# axiom_beta_plugin_module_1xHDMI.net
KiCad netlist of a schematic drawn in EAGLE
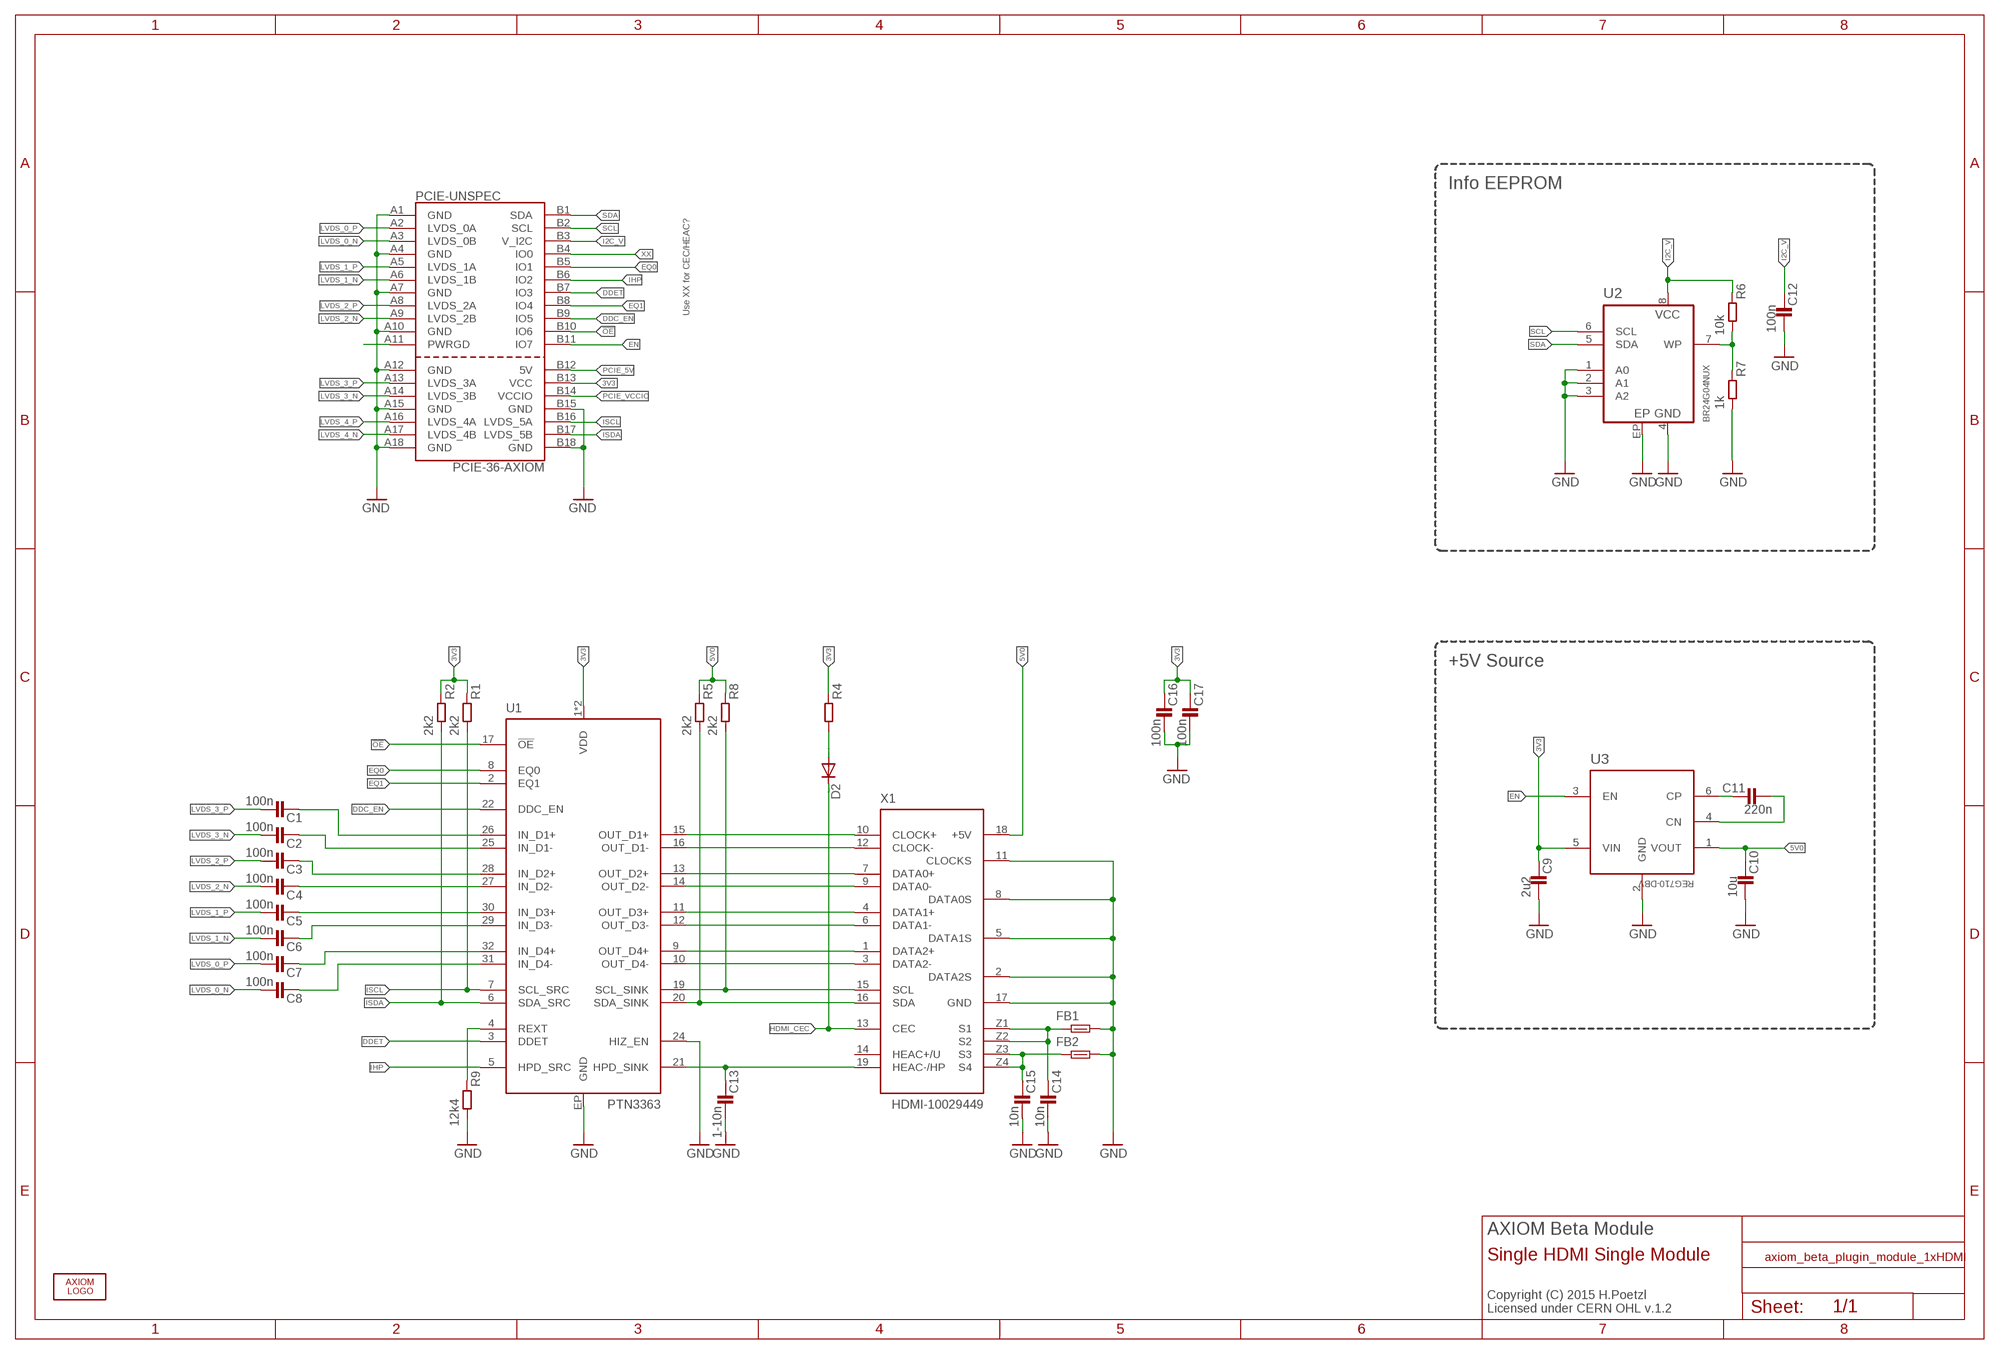
[diagram p0: schematic, sheet 1]

(export (version "E")
  (design (tool "Eeschema 10.0.6"))
  (components
    (comp (ref "C1")
      (value "100n")
      (footprint "eagle-import:0402-C")
      (libsource (lib "eagle-import") (part "C0402-C"))
    )
    (comp (ref "C2")
      (value "100n")
      (footprint "eagle-import:0402-C")
      (libsource (lib "eagle-import") (part "C0402-C"))
    )
    (comp (ref "C3")
      (value "100n")
      (footprint "eagle-import:0402-C")
      (libsource (lib "eagle-import") (part "C0402-C"))
    )
    (comp (ref "C4")
      (value "100n")
      (footprint "eagle-import:0402-C")
      (libsource (lib "eagle-import") (part "C0402-C"))
    )
    (comp (ref "C5")
      (value "100n")
      (footprint "eagle-import:0402-C")
      (libsource (lib "eagle-import") (part "C0402-C"))
    )
    (comp (ref "C6")
      (value "100n")
      (footprint "eagle-import:0402-C")
      (libsource (lib "eagle-import") (part "C0402-C"))
    )
    (comp (ref "C7")
      (value "100n")
      (footprint "eagle-import:0402-C")
      (libsource (lib "eagle-import") (part "C0402-C"))
    )
    (comp (ref "C8")
      (value "100n")
      (footprint "eagle-import:0402-C")
      (libsource (lib "eagle-import") (part "C0402-C"))
    )
    (comp (ref "C9")
      (value "2u2")
      (footprint "eagle-import:0603-B")
      (libsource (lib "eagle-import") (part "C0603-B"))
    )
    (comp (ref "C10")
      (value "10u")
      (footprint "eagle-import:0603-B")
      (libsource (lib "eagle-import") (part "C0603-B"))
    )
    (comp (ref "C11")
      (value "220n")
      (footprint "eagle-import:0603-B")
      (libsource (lib "eagle-import") (part "C0603-B"))
    )
    (comp (ref "C12")
      (value "100n")
      (footprint "eagle-import:0402-B")
      (libsource (lib "eagle-import") (part "C0402-B"))
    )
    (comp (ref "C13")
      (value "1-10n")
      (footprint "eagle-import:0402-B")
      (libsource (lib "eagle-import") (part "C0402-B"))
    )
    (comp (ref "C14")
      (value "10n")
      (footprint "eagle-import:0402-B")
      (libsource (lib "eagle-import") (part "C0402-B"))
    )
    (comp (ref "C15")
      (value "10n")
      (footprint "eagle-import:0402-B")
      (libsource (lib "eagle-import") (part "C0402-B"))
    )
    (comp (ref "C16")
      (value "100n")
      (footprint "eagle-import:0402-B")
      (libsource (lib "eagle-import") (part "C0402-B"))
    )
    (comp (ref "C17")
      (value "100n")
      (footprint "eagle-import:0402-B")
      (libsource (lib "eagle-import") (part "C0402-B"))
    )
    (comp (ref "D2")
      (value "DIODE-SOD523")
      (footprint "eagle-import:SOD523")
      (libsource (lib "eagle-import") (part "DIODE-SOD523"))
    )
    (comp (ref "FB1")
      (value "FB0603-B")
      (footprint "eagle-import:0603-B")
      (libsource (lib "eagle-import") (part "FB0603-B"))
    )
    (comp (ref "FB2")
      (value "FB0603-B")
      (footprint "eagle-import:0603-B")
      (libsource (lib "eagle-import") (part "FB0603-B"))
    )
    (comp (ref "PCIE-UNSPEC")
      (value "PCIE-36-AXIOM")
      (footprint "eagle-import:PCIE-36-AXIOM")
      (libsource (lib "eagle-import") (part "PCIE-36-AXIOM"))
    )
    (comp (ref "R1")
      (value "2k2")
      (footprint "eagle-import:0402-B")
      (libsource (lib "eagle-import") (part "R0402-B"))
    )
    (comp (ref "R2")
      (value "2k2")
      (footprint "eagle-import:0402-B")
      (libsource (lib "eagle-import") (part "R0402-B"))
    )
    (comp (ref "R4")
      (value "R0402-B")
      (footprint "eagle-import:0402-B")
      (libsource (lib "eagle-import") (part "R0402-B"))
    )
    (comp (ref "R5")
      (value "2k2")
      (footprint "eagle-import:0402-B")
      (libsource (lib "eagle-import") (part "R0402-B"))
    )
    (comp (ref "R6")
      (value "10k")
      (footprint "eagle-import:0402-B")
      (libsource (lib "eagle-import") (part "R0402-B"))
    )
    (comp (ref "R7")
      (value "1k")
      (footprint "eagle-import:0402-B")
      (libsource (lib "eagle-import") (part "R0402-B"))
    )
    (comp (ref "R8")
      (value "2k2")
      (footprint "eagle-import:0402-B")
      (libsource (lib "eagle-import") (part "R0402-B"))
    )
    (comp (ref "R9")
      (value "12k4")
      (footprint "eagle-import:0402-B")
      (libsource (lib "eagle-import") (part "R0402-B"))
    )
    (comp (ref "U$1")
      (value "AXIOM_LOGO459X70")
      (footprint "eagle-import:AXIOM_LOGO_459X70")
      (libsource (lib "eagle-import") (part "AXIOM_LOGO459X70"))
    )
    (comp (ref "U1")
      (value "PTN3363")
      (footprint "eagle-import:HVQFN32")
      (libsource (lib "eagle-import") (part "PTN3363"))
    )
    (comp (ref "U2")
      (value "BR24G04NUX")
      (footprint "eagle-import:DFN200X300X100-9N")
      (libsource (lib "eagle-import") (part "BR24G04NUX"))
    )
    (comp (ref "U3")
      (value "REG710-DBV")
      (footprint "eagle-import:DBV")
      (libsource (lib "eagle-import") (part "REG710-DBV"))
    )
    (comp (ref "X1")
      (value "HDMI-10029449")
      (footprint "eagle-import:10029449-X01XLF")
      (libsource (lib "eagle-import") (part "HDMI-10029449"))
    )
  )
  (nets
    (net (code "1") (name "/~{OE}") (class "Default")
      (node (ref "PCIE-UNSPEC") (pin "B10") (pinfunction "IO6_B10") (pintype "passive"))
      (node (ref "U1") (pin "17") (pinfunction "~{OE}_17") (pintype "bidirectional"))
    )
    (net (code "2") (name "3V3") (class "Default")
      (node (ref "C16") (pin "1") (pinfunction "1_1") (pintype "passive"))
      (node (ref "C17") (pin "1") (pinfunction "1_1") (pintype "passive"))
      (node (ref "C9") (pin "1") (pinfunction "1_1") (pintype "passive"))
      (node (ref "PCIE-UNSPEC") (pin "B13") (pinfunction "VCC_B13") (pintype "passive"))
      (node (ref "R1") (pin "1") (pinfunction "1_1") (pintype "passive"))
      (node (ref "R2") (pin "1") (pinfunction "1_1") (pintype "passive"))
      (node (ref "R4") (pin "1") (pinfunction "1_1") (pintype "passive"))
      (node (ref "U1") (pin "1") (pinfunction "VDD_1") (pintype "power_in"))
      (node (ref "U1") (pin "18") (pinfunction "VDD_18") (pintype "power_in"))
      (node (ref "U3") (pin "5") (pinfunction "VIN_5") (pintype "power_in"))
    )
    (net (code "3") (name "5V0") (class "Default")
      (node (ref "C10") (pin "1") (pinfunction "1_1") (pintype "passive"))
      (node (ref "R5") (pin "1") (pinfunction "1_1") (pintype "passive"))
      (node (ref "R8") (pin "1") (pinfunction "1_1") (pintype "passive"))
      (node (ref "U3") (pin "1") (pinfunction "VOUT_1") (pintype "output"))
      (node (ref "X1") (pin "18") (pinfunction "+5V_18") (pintype "power_in"))
    )
    (net (code "4") (name "DDC_EN") (class "Default")
      (node (ref "PCIE-UNSPEC") (pin "B9") (pinfunction "IO5_B9") (pintype "passive"))
      (node (ref "U1") (pin "22") (pinfunction "DDC_EN_22") (pintype "bidirectional"))
    )
    (net (code "5") (name "DDET") (class "Default")
      (node (ref "PCIE-UNSPEC") (pin "B7") (pinfunction "IO3_B7") (pintype "passive"))
      (node (ref "U1") (pin "3") (pinfunction "DDET_3") (pintype "bidirectional"))
    )
    (net (code "6") (name "EN") (class "Default")
      (node (ref "PCIE-UNSPEC") (pin "B11") (pinfunction "IO7_B11") (pintype "passive"))
      (node (ref "U3") (pin "3") (pinfunction "EN_3") (pintype "input"))
    )
    (net (code "7") (name "EQ0") (class "Default")
      (node (ref "PCIE-UNSPEC") (pin "B5") (pinfunction "IO1_B5") (pintype "passive"))
      (node (ref "U1") (pin "8") (pinfunction "EQ0_8") (pintype "bidirectional"))
    )
    (net (code "8") (name "EQ1") (class "Default")
      (node (ref "PCIE-UNSPEC") (pin "B8") (pinfunction "IO4_B8") (pintype "passive"))
      (node (ref "U1") (pin "2") (pinfunction "EQ1_2") (pintype "bidirectional"))
    )
    (net (code "9") (name "GND") (class "Default")
      (node (ref "C10") (pin "2") (pinfunction "2_2") (pintype "passive"))
      (node (ref "C12") (pin "2") (pinfunction "2_2") (pintype "passive"))
      (node (ref "C13") (pin "2") (pinfunction "2_2") (pintype "passive"))
      (node (ref "C14") (pin "2") (pinfunction "2_2") (pintype "passive"))
      (node (ref "C15") (pin "2") (pinfunction "2_2") (pintype "passive"))
      (node (ref "C16") (pin "2") (pinfunction "2_2") (pintype "passive"))
      (node (ref "C17") (pin "2") (pinfunction "2_2") (pintype "passive"))
      (node (ref "C9") (pin "2") (pinfunction "2_2") (pintype "passive"))
      (node (ref "FB1") (pin "2") (pinfunction "2_2") (pintype "passive"))
      (node (ref "FB2") (pin "2") (pinfunction "2_2") (pintype "passive"))
      (node (ref "PCIE-UNSPEC") (pin "A1") (pinfunction "GND_A1") (pintype "passive"))
      (node (ref "PCIE-UNSPEC") (pin "A10") (pinfunction "GND_A10") (pintype "passive"))
      (node (ref "PCIE-UNSPEC") (pin "A12") (pinfunction "GND_A12") (pintype "passive"))
      (node (ref "PCIE-UNSPEC") (pin "A15") (pinfunction "GND_A15") (pintype "passive"))
      (node (ref "PCIE-UNSPEC") (pin "A18") (pinfunction "GND_A18") (pintype "passive"))
      (node (ref "PCIE-UNSPEC") (pin "A4") (pinfunction "GND_A4") (pintype "passive"))
      (node (ref "PCIE-UNSPEC") (pin "A7") (pinfunction "GND_A7") (pintype "passive"))
      (node (ref "PCIE-UNSPEC") (pin "B15") (pinfunction "GND_B15") (pintype "passive"))
      (node (ref "PCIE-UNSPEC") (pin "B18") (pinfunction "GND_B18") (pintype "passive"))
      (node (ref "R7") (pin "2") (pinfunction "2_2") (pintype "passive"))
      (node (ref "R9") (pin "2") (pinfunction "2_2") (pintype "passive"))
      (node (ref "U1") (pin "24") (pinfunction "HIZ_EN_24") (pintype "bidirectional"))
      (node (ref "U1") (pin "EP") (pinfunction "GND_EP") (pintype "bidirectional"))
      (node (ref "U2") (pin "1") (pinfunction "A0_1") (pintype "input"))
      (node (ref "U2") (pin "2") (pinfunction "A1_2") (pintype "input"))
      (node (ref "U2") (pin "3") (pinfunction "A2_3") (pintype "input"))
      (node (ref "U2") (pin "4") (pinfunction "GND_4") (pintype "passive"))
      (node (ref "U2") (pin "EP") (pinfunction "EP_EP") (pintype "passive"))
      (node (ref "U3") (pin "2") (pinfunction "GND_2") (pintype "passive"))
      (node (ref "X1") (pin "11") (pinfunction "CLOCKS_11") (pintype "power_in"))
      (node (ref "X1") (pin "17") (pinfunction "GND_17") (pintype "bidirectional"))
      (node (ref "X1") (pin "2") (pinfunction "DATA2S_2") (pintype "power_in"))
      (node (ref "X1") (pin "5") (pinfunction "DATA1S_5") (pintype "power_in"))
      (node (ref "X1") (pin "8") (pinfunction "DATA0S_8") (pintype "power_in"))
    )
    (net (code "10") (name "HDMI_CEC") (class "Default")
      (node (ref "D2") (pin "C") (pinfunction "C_C") (pintype "passive"))
      (node (ref "X1") (pin "13") (pinfunction "CEC_13") (pintype "bidirectional"))
    )
    (net (code "11") (name "I2C_V") (class "Default")
      (node (ref "C12") (pin "1") (pinfunction "1_1") (pintype "passive"))
      (node (ref "PCIE-UNSPEC") (pin "B3") (pinfunction "V_I2C_B3") (pintype "passive"))
      (node (ref "R6") (pin "1") (pinfunction "1_1") (pintype "passive"))
      (node (ref "U2") (pin "8") (pinfunction "VCC_8") (pintype "power_in"))
    )
    (net (code "12") (name "IHP") (class "Default")
      (node (ref "PCIE-UNSPEC") (pin "B6") (pinfunction "IO2_B6") (pintype "passive"))
      (node (ref "U1") (pin "5") (pinfunction "HPD_SRC_5") (pintype "bidirectional"))
    )
    (net (code "13") (name "ISCL") (class "Default")
      (node (ref "PCIE-UNSPEC") (pin "B16") (pinfunction "LVDS_5A_B16") (pintype "passive"))
      (node (ref "R1") (pin "2") (pinfunction "2_2") (pintype "passive"))
      (node (ref "U1") (pin "7") (pinfunction "SCL_SRC_7") (pintype "bidirectional"))
    )
    (net (code "14") (name "ISDA") (class "Default")
      (node (ref "PCIE-UNSPEC") (pin "B17") (pinfunction "LVDS_5B_B17") (pintype "passive"))
      (node (ref "R2") (pin "2") (pinfunction "2_2") (pintype "passive"))
      (node (ref "U1") (pin "6") (pinfunction "SDA_SRC_6") (pintype "bidirectional"))
    )
    (net (code "15") (name "LVDS_0_N") (class "Default")
      (node (ref "C8") (pin "2") (pinfunction "2_2") (pintype "passive"))
      (node (ref "PCIE-UNSPEC") (pin "A3") (pinfunction "LVDS_0B_A3") (pintype "passive"))
    )
    (net (code "16") (name "LVDS_0_P") (class "Default")
      (node (ref "C7") (pin "2") (pinfunction "2_2") (pintype "passive"))
      (node (ref "PCIE-UNSPEC") (pin "A2") (pinfunction "LVDS_0A_A2") (pintype "passive"))
    )
    (net (code "17") (name "LVDS_1_N") (class "Default")
      (node (ref "C6") (pin "2") (pinfunction "2_2") (pintype "passive"))
      (node (ref "PCIE-UNSPEC") (pin "A6") (pinfunction "LVDS_1B_A6") (pintype "passive"))
    )
    (net (code "18") (name "LVDS_1_P") (class "Default")
      (node (ref "C5") (pin "2") (pinfunction "2_2") (pintype "passive"))
      (node (ref "PCIE-UNSPEC") (pin "A5") (pinfunction "LVDS_1A_A5") (pintype "passive"))
    )
    (net (code "19") (name "LVDS_2_N") (class "Default")
      (node (ref "C4") (pin "2") (pinfunction "2_2") (pintype "passive"))
      (node (ref "PCIE-UNSPEC") (pin "A9") (pinfunction "LVDS_2B_A9") (pintype "passive"))
    )
    (net (code "20") (name "LVDS_2_P") (class "Default")
      (node (ref "C3") (pin "2") (pinfunction "2_2") (pintype "passive"))
      (node (ref "PCIE-UNSPEC") (pin "A8") (pinfunction "LVDS_2A_A8") (pintype "passive"))
    )
    (net (code "21") (name "LVDS_3_N") (class "Default")
      (node (ref "C2") (pin "2") (pinfunction "2_2") (pintype "passive"))
      (node (ref "PCIE-UNSPEC") (pin "A14") (pinfunction "LVDS_3B_A14") (pintype "passive"))
    )
    (net (code "22") (name "LVDS_3_P") (class "Default")
      (node (ref "C1") (pin "2") (pinfunction "2_2") (pintype "passive"))
      (node (ref "PCIE-UNSPEC") (pin "A13") (pinfunction "LVDS_3A_A13") (pintype "passive"))
    )
    (net (code "23") (name "LVDS_4_N") (class "Default")
      (node (ref "PCIE-UNSPEC") (pin "A17") (pinfunction "LVDS_4B_A17") (pintype "passive"))
    )
    (net (code "24") (name "LVDS_4_P") (class "Default")
      (node (ref "PCIE-UNSPEC") (pin "A16") (pinfunction "LVDS_4A_A16") (pintype "passive"))
    )
    (net (code "25") (name "Net-(D2-PadA)") (class "Default")
      (node (ref "D2") (pin "A") (pinfunction "A_A") (pintype "passive"))
      (node (ref "R4") (pin "2") (pinfunction "2_2") (pintype "passive"))
    )
    (net (code "26") (name "Net-(U1-HPD_SINK)") (class "Default")
      (node (ref "C13") (pin "1") (pinfunction "1_1") (pintype "passive"))
      (node (ref "U1") (pin "21") (pinfunction "HPD_SINK_21") (pintype "bidirectional"))
      (node (ref "X1") (pin "19") (pinfunction "HEAC-/HP_19") (pintype "bidirectional"))
    )
    (net (code "27") (name "Net-(U1-IN_D1+)") (class "Default")
      (node (ref "C1") (pin "1") (pinfunction "1_1") (pintype "passive"))
      (node (ref "U1") (pin "26") (pinfunction "IN_D1+_26") (pintype "bidirectional"))
    )
    (net (code "28") (name "Net-(U1-IN_D1-)") (class "Default")
      (node (ref "C2") (pin "1") (pinfunction "1_1") (pintype "passive"))
      (node (ref "U1") (pin "25") (pinfunction "IN_D1-_25") (pintype "bidirectional"))
    )
    (net (code "29") (name "Net-(U1-IN_D2+)") (class "Default")
      (node (ref "C3") (pin "1") (pinfunction "1_1") (pintype "passive"))
      (node (ref "U1") (pin "28") (pinfunction "IN_D2+_28") (pintype "bidirectional"))
    )
    (net (code "30") (name "Net-(U1-IN_D2-)") (class "Default")
      (node (ref "C4") (pin "1") (pinfunction "1_1") (pintype "passive"))
      (node (ref "U1") (pin "27") (pinfunction "IN_D2-_27") (pintype "bidirectional"))
    )
    (net (code "31") (name "Net-(U1-IN_D3+)") (class "Default")
      (node (ref "C5") (pin "1") (pinfunction "1_1") (pintype "passive"))
      (node (ref "U1") (pin "30") (pinfunction "IN_D3+_30") (pintype "bidirectional"))
    )
    (net (code "32") (name "Net-(U1-IN_D3-)") (class "Default")
      (node (ref "C6") (pin "1") (pinfunction "1_1") (pintype "passive"))
      (node (ref "U1") (pin "29") (pinfunction "IN_D3-_29") (pintype "bidirectional"))
    )
    (net (code "33") (name "Net-(U1-IN_D4+)") (class "Default")
      (node (ref "C7") (pin "1") (pinfunction "1_1") (pintype "passive"))
      (node (ref "U1") (pin "32") (pinfunction "IN_D4+_32") (pintype "bidirectional"))
    )
    (net (code "34") (name "Net-(U1-IN_D4-)") (class "Default")
      (node (ref "C8") (pin "1") (pinfunction "1_1") (pintype "passive"))
      (node (ref "U1") (pin "31") (pinfunction "IN_D4-_31") (pintype "bidirectional"))
    )
    (net (code "35") (name "Net-(U1-OUT_D1+)") (class "Default")
      (node (ref "U1") (pin "15") (pinfunction "OUT_D1+_15") (pintype "bidirectional"))
      (node (ref "X1") (pin "10") (pinfunction "CLOCK+_10") (pintype "bidirectional"))
    )
    (net (code "36") (name "Net-(U1-OUT_D1-)") (class "Default")
      (node (ref "U1") (pin "16") (pinfunction "OUT_D1-_16") (pintype "bidirectional"))
      (node (ref "X1") (pin "12") (pinfunction "CLOCK-_12") (pintype "bidirectional"))
    )
    (net (code "37") (name "Net-(U1-OUT_D2+)") (class "Default")
      (node (ref "U1") (pin "13") (pinfunction "OUT_D2+_13") (pintype "bidirectional"))
      (node (ref "X1") (pin "7") (pinfunction "DATA0+_7") (pintype "bidirectional"))
    )
    (net (code "38") (name "Net-(U1-OUT_D2-)") (class "Default")
      (node (ref "U1") (pin "14") (pinfunction "OUT_D2-_14") (pintype "bidirectional"))
      (node (ref "X1") (pin "9") (pinfunction "DATA0-_9") (pintype "bidirectional"))
    )
    (net (code "39") (name "Net-(U1-OUT_D3+)") (class "Default")
      (node (ref "U1") (pin "11") (pinfunction "OUT_D3+_11") (pintype "bidirectional"))
      (node (ref "X1") (pin "4") (pinfunction "DATA1+_4") (pintype "bidirectional"))
    )
    (net (code "40") (name "Net-(U1-OUT_D3-)") (class "Default")
      (node (ref "U1") (pin "12") (pinfunction "OUT_D3-_12") (pintype "bidirectional"))
      (node (ref "X1") (pin "6") (pinfunction "DATA1-_6") (pintype "bidirectional"))
    )
    (net (code "41") (name "Net-(U1-OUT_D4+)") (class "Default")
      (node (ref "U1") (pin "9") (pinfunction "OUT_D4+_9") (pintype "bidirectional"))
      (node (ref "X1") (pin "1") (pinfunction "DATA2+_1") (pintype "bidirectional"))
    )
    (net (code "42") (name "Net-(U1-OUT_D4-)") (class "Default")
      (node (ref "U1") (pin "10") (pinfunction "OUT_D4-_10") (pintype "bidirectional"))
      (node (ref "X1") (pin "3") (pinfunction "DATA2-_3") (pintype "bidirectional"))
    )
    (net (code "43") (name "Net-(U1-REXT)") (class "Default")
      (node (ref "R9") (pin "1") (pinfunction "1_1") (pintype "passive"))
      (node (ref "U1") (pin "4") (pinfunction "REXT_4") (pintype "bidirectional"))
    )
    (net (code "44") (name "Net-(U1-SCL_SINK)") (class "Default")
      (node (ref "R8") (pin "2") (pinfunction "2_2") (pintype "passive"))
      (node (ref "U1") (pin "19") (pinfunction "SCL_SINK_19") (pintype "bidirectional"))
      (node (ref "X1") (pin "15") (pinfunction "SCL_15") (pintype "bidirectional"))
    )
    (net (code "45") (name "Net-(U1-SDA_SINK)") (class "Default")
      (node (ref "R5") (pin "2") (pinfunction "2_2") (pintype "passive"))
      (node (ref "U1") (pin "20") (pinfunction "SDA_SINK_20") (pintype "bidirectional"))
      (node (ref "X1") (pin "16") (pinfunction "SDA_16") (pintype "bidirectional"))
    )
    (net (code "46") (name "Net-(U2-WP)") (class "Default")
      (node (ref "R6") (pin "2") (pinfunction "2_2") (pintype "passive"))
      (node (ref "R7") (pin "1") (pinfunction "1_1") (pintype "passive"))
      (node (ref "U2") (pin "7") (pinfunction "WP_7") (pintype "input"))
    )
    (net (code "47") (name "Net-(U3-CN)") (class "Default")
      (node (ref "C11") (pin "2") (pinfunction "2_2") (pintype "passive"))
      (node (ref "U3") (pin "4") (pinfunction "CN_4") (pintype "power_in"))
    )
    (net (code "48") (name "Net-(U3-CP)") (class "Default")
      (node (ref "C11") (pin "1") (pinfunction "1_1") (pintype "passive"))
      (node (ref "U3") (pin "6") (pinfunction "CP_6") (pintype "output"))
    )
    (net (code "49") (name "Net-(X1-S1)") (class "Default")
      (node (ref "C14") (pin "1") (pinfunction "1_1") (pintype "passive"))
      (node (ref "FB1") (pin "1") (pinfunction "1_1") (pintype "passive"))
      (node (ref "X1") (pin "Z1") (pinfunction "S1_Z1") (pintype "power_in"))
      (node (ref "X1") (pin "Z2") (pinfunction "S2_Z2") (pintype "power_in"))
    )
    (net (code "50") (name "Net-(X1-S3)") (class "Default")
      (node (ref "C15") (pin "1") (pinfunction "1_1") (pintype "passive"))
      (node (ref "FB2") (pin "1") (pinfunction "1_1") (pintype "passive"))
      (node (ref "X1") (pin "Z3") (pinfunction "S3_Z3") (pintype "power_in"))
      (node (ref "X1") (pin "Z4") (pinfunction "S4_Z4") (pintype "power_in"))
    )
    (net (code "51") (name "PCIE_5V") (class "Default")
      (node (ref "PCIE-UNSPEC") (pin "B12") (pinfunction "5V_B12") (pintype "passive"))
    )
    (net (code "52") (name "PCIE_VCCIO") (class "Default")
      (node (ref "PCIE-UNSPEC") (pin "B14") (pinfunction "VCCIO_B14") (pintype "passive"))
    )
    (net (code "53") (name "SCL") (class "Default")
      (node (ref "PCIE-UNSPEC") (pin "B2") (pinfunction "SCL_B2") (pintype "passive"))
      (node (ref "U2") (pin "6") (pinfunction "SCL_6") (pintype "input"))
    )
    (net (code "54") (name "SDA") (class "Default")
      (node (ref "PCIE-UNSPEC") (pin "B1") (pinfunction "SDA_B1") (pintype "passive"))
      (node (ref "U2") (pin "5") (pinfunction "SDA_5") (pintype "bidirectional"))
    )
    (net (code "55") (name "XX") (class "Default")
      (node (ref "PCIE-UNSPEC") (pin "B4") (pinfunction "IO0_B4") (pintype "passive"))
    )
    (net (code "56") (name "unconnected-(PCIE-UNSPEC-PWRGD-PadA11)") (class "Default")
      (node (ref "PCIE-UNSPEC") (pin "A11") (pinfunction "PWRGD_A11") (pintype "passive"))
    )
    (net (code "57") (name "unconnected-(X1-HEAC+{slash}U-Pad14)") (class "Default")
      (node (ref "X1") (pin "14") (pinfunction "HEAC+/U_14") (pintype "bidirectional"))
    )
  )
)
